# butt_blaster.net
KiCad netlist of a schematic drawn in EAGLE
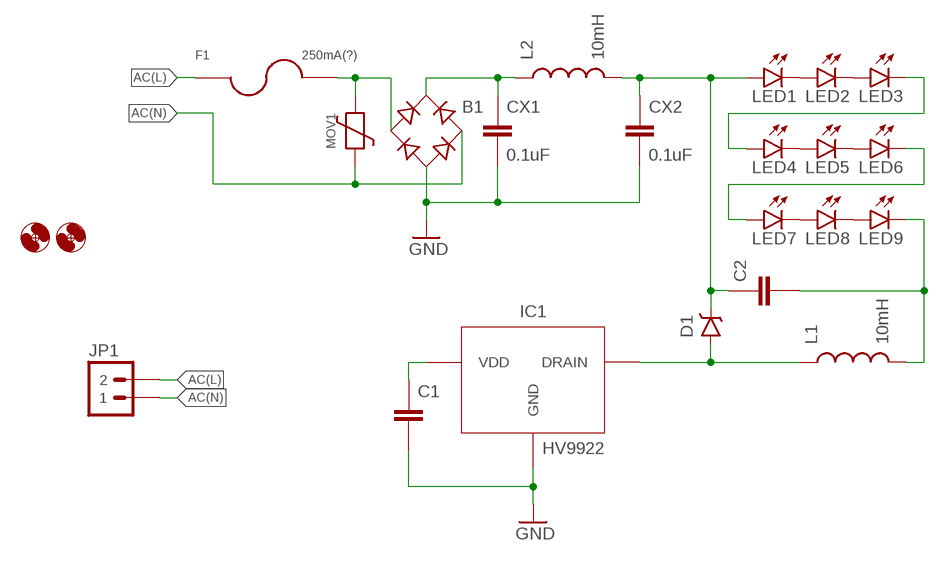
[diagram p0: schematic, sheet 1]

(export (version "E")
  (design (tool "Eeschema 10.0.6"))
  (components
    (comp (ref "B1")
      (value "RB1ANOSUCK")
      (footprint "eagle-import:RB1A-NOSUCK")
      (libsource (lib "eagle-import") (part "RB1ANOSUCK"))
    )
    (comp (ref "C1")
      (value "CAPACITOR-CERAMIC025-024X044")
      (footprint "eagle-import:C025-024X044")
      (libsource (lib "eagle-import") (part "CAPACITOR-CERAMIC025-024X044"))
    )
    (comp (ref "C2")
      (value "CAPACITOR-CERAMIC025-024X044")
      (footprint "eagle-import:C025-024X044")
      (libsource (lib "eagle-import") (part "CAPACITOR-CERAMIC025-024X044"))
    )
    (comp (ref "CX1")
      (value "0.1uF")
      (footprint "eagle-import:XC10B5")
      (libsource (lib "eagle-import") (part "CXXC10B5"))
    )
    (comp (ref "CX2")
      (value "0.1uF")
      (footprint "eagle-import:XC10B5")
      (libsource (lib "eagle-import") (part "CXXC10B5"))
    )
    (comp (ref "D1")
      (value "DIODE-SCHOTTKYPTH-7.68MM")
      (footprint "eagle-import:DIODE-7.68MM")
      (libsource (lib "eagle-import") (part "DIODE-SCHOTTKYPTH-7.68MM"))
    )
    (comp (ref "F1")
      (value "250mA(?)")
      (footprint "eagle-import:TR5")
      (libsource (lib "eagle-import") (part "FUSETR5"))
    )
    (comp (ref "H1")
      (value "HOLE#2")
      (footprint "eagle-import:HOLE-#2")
      (libsource (lib "eagle-import") (part "HOLE#2"))
    )
    (comp (ref "H2")
      (value "HOLE#2")
      (footprint "eagle-import:HOLE-#2")
      (libsource (lib "eagle-import") (part "HOLE#2"))
    )
    (comp (ref "IC1")
      (value "HV9922")
      (footprint "eagle-import:TO-92")
      (libsource (lib "eagle-import") (part "HV9922"))
    )
    (comp (ref "JP1")
      (value "M025MM")
      (footprint "eagle-import:SCREWTERMINAL-5MM-2")
      (libsource (lib "eagle-import") (part "M025MM"))
    )
    (comp (ref "L1")
      (value "10mH")
      (footprint "eagle-import:RLB0912")
      (libsource (lib "eagle-import") (part "INDUCTORRLB0912"))
    )
    (comp (ref "L2")
      (value "10mH")
      (footprint "eagle-import:INDUCTOR-AXIAL-PTH-10.16MM")
      (libsource (lib "eagle-import") (part "INDUCTORAXIAL-PTH-10.16MM"))
    )
    (comp (ref "LED1")
      (value "LED5MM_SHORTPADS")
      (footprint "eagle-import:LED5MM_SHORTPADS")
      (libsource (lib "eagle-import") (part "LED5MM_SHORTPADS"))
    )
    (comp (ref "LED2")
      (value "LED5MM_SHORTPADS")
      (footprint "eagle-import:LED5MM_SHORTPADS")
      (libsource (lib "eagle-import") (part "LED5MM_SHORTPADS"))
    )
    (comp (ref "LED3")
      (value "LED5MM_SHORTPADS")
      (footprint "eagle-import:LED5MM_SHORTPADS")
      (libsource (lib "eagle-import") (part "LED5MM_SHORTPADS"))
    )
    (comp (ref "LED4")
      (value "LED5MM_SHORTPADS")
      (footprint "eagle-import:LED5MM_SHORTPADS")
      (libsource (lib "eagle-import") (part "LED5MM_SHORTPADS"))
    )
    (comp (ref "LED5")
      (value "LED5MM_SHORTPADS")
      (footprint "eagle-import:LED5MM_SHORTPADS")
      (libsource (lib "eagle-import") (part "LED5MM_SHORTPADS"))
    )
    (comp (ref "LED6")
      (value "LED5MM_SHORTPADS")
      (footprint "eagle-import:LED5MM_SHORTPADS")
      (libsource (lib "eagle-import") (part "LED5MM_SHORTPADS"))
    )
    (comp (ref "LED7")
      (value "LED5MM_SHORTPADS")
      (footprint "eagle-import:LED5MM_SHORTPADS")
      (libsource (lib "eagle-import") (part "LED5MM_SHORTPADS"))
    )
    (comp (ref "LED8")
      (value "LED5MM_SHORTPADS")
      (footprint "eagle-import:LED5MM_SHORTPADS")
      (libsource (lib "eagle-import") (part "LED5MM_SHORTPADS"))
    )
    (comp (ref "LED9")
      (value "LED5MM_SHORTPADS")
      (footprint "eagle-import:LED5MM_SHORTPADS")
      (libsource (lib "eagle-import") (part "LED5MM_SHORTPADS"))
    )
    (comp (ref "MOV1")
      (value "VARISITORVAR-5.08MM-PTH")
      (footprint "eagle-import:VAR-5.08MM-PTH")
      (libsource (lib "eagle-import") (part "VARISITORVAR-5.08MM-PTH"))
    )
  )
  (nets
    (net (code "1") (name "AC(L)") (class "Default")
      (node (ref "F1") (pin "1") (pinfunction "1_1") (pintype "bidirectional"))
      (node (ref "JP1") (pin "2") (pinfunction "2_2") (pintype "passive"))
    )
    (net (code "2") (name "AC(N)") (class "Default")
      (node (ref "B1") (pin "AC2") (pinfunction "AC2_AC2") (pintype "passive"))
      (node (ref "JP1") (pin "1") (pinfunction "1_1") (pintype "passive"))
      (node (ref "MOV1") (pin "1") (pinfunction "P$1_1") (pintype "bidirectional"))
    )
    (net (code "3") (name "GND") (class "Default")
      (node (ref "B1") (pin "-") (pinfunction "-_-") (pintype "passive"))
      (node (ref "C1") (pin "2") (pinfunction "2_2") (pintype "passive"))
      (node (ref "CX1") (pin "2") (pinfunction "2_2") (pintype "passive"))
      (node (ref "CX2") (pin "2") (pinfunction "2_2") (pintype "passive"))
      (node (ref "IC1") (pin "2") (pinfunction "GND_2") (pintype "bidirectional"))
    )
    (net (code "4") (name "Net-(D1-C)") (class "Default")
      (node (ref "C2") (pin "1") (pinfunction "1_1") (pintype "passive"))
      (node (ref "CX2") (pin "1") (pinfunction "1_1") (pintype "passive"))
      (node (ref "D1") (pin "K") (pinfunction "C_K") (pintype "passive"))
      (node (ref "L2") (pin "P$2") (pinfunction "2_P$2") (pintype "passive"))
      (node (ref "LED1") (pin "A") (pinfunction "A_A") (pintype "passive"))
    )
    (net (code "5") (name "Net-(IC1-DRAIN)") (class "Default")
      (node (ref "D1") (pin "A") (pinfunction "A_A") (pintype "passive"))
      (node (ref "IC1") (pin "1") (pinfunction "DRAIN_1") (pintype "bidirectional"))
      (node (ref "L1") (pin "1") (pinfunction "1_1") (pintype "passive"))
    )
    (net (code "6") (name "Net-(IC1-VDD)") (class "Default")
      (node (ref "C1") (pin "1") (pinfunction "1_1") (pintype "passive"))
      (node (ref "IC1") (pin "3") (pinfunction "VDD_3") (pintype "bidirectional"))
    )
    (net (code "7") (name "Net-(L2-1)") (class "Default")
      (node (ref "B1") (pin "+") (pinfunction "+_+") (pintype "passive"))
      (node (ref "CX1") (pin "1") (pinfunction "1_1") (pintype "passive"))
      (node (ref "L2") (pin "P$1") (pinfunction "1_P$1") (pintype "passive"))
    )
    (net (code "8") (name "Net-(LED1-C)") (class "Default")
      (node (ref "LED1") (pin "K") (pinfunction "C_K") (pintype "passive"))
      (node (ref "LED2") (pin "A") (pinfunction "A_A") (pintype "passive"))
    )
    (net (code "9") (name "Net-(LED2-C)") (class "Default")
      (node (ref "LED2") (pin "K") (pinfunction "C_K") (pintype "passive"))
      (node (ref "LED3") (pin "A") (pinfunction "A_A") (pintype "passive"))
    )
    (net (code "10") (name "Net-(LED3-C)") (class "Default")
      (node (ref "LED3") (pin "K") (pinfunction "C_K") (pintype "passive"))
      (node (ref "LED4") (pin "A") (pinfunction "A_A") (pintype "passive"))
    )
    (net (code "11") (name "Net-(LED4-C)") (class "Default")
      (node (ref "LED4") (pin "K") (pinfunction "C_K") (pintype "passive"))
      (node (ref "LED5") (pin "A") (pinfunction "A_A") (pintype "passive"))
    )
    (net (code "12") (name "Net-(LED5-C)") (class "Default")
      (node (ref "LED5") (pin "K") (pinfunction "C_K") (pintype "passive"))
      (node (ref "LED6") (pin "A") (pinfunction "A_A") (pintype "passive"))
    )
    (net (code "13") (name "Net-(LED6-C)") (class "Default")
      (node (ref "LED6") (pin "K") (pinfunction "C_K") (pintype "passive"))
      (node (ref "LED7") (pin "A") (pinfunction "A_A") (pintype "passive"))
    )
    (net (code "14") (name "Net-(LED7-C)") (class "Default")
      (node (ref "LED7") (pin "K") (pinfunction "C_K") (pintype "passive"))
      (node (ref "LED8") (pin "A") (pinfunction "A_A") (pintype "passive"))
    )
    (net (code "15") (name "Net-(LED8-C)") (class "Default")
      (node (ref "LED8") (pin "K") (pinfunction "C_K") (pintype "passive"))
      (node (ref "LED9") (pin "A") (pinfunction "A_A") (pintype "passive"))
    )
    (net (code "16") (name "Net-(LED9-C)") (class "Default")
      (node (ref "C2") (pin "2") (pinfunction "2_2") (pintype "passive"))
      (node (ref "L1") (pin "2") (pinfunction "2_2") (pintype "passive"))
      (node (ref "LED9") (pin "K") (pinfunction "C_K") (pintype "passive"))
    )
    (net (code "17") (name "Net-(MOV1-P$2)") (class "Default")
      (node (ref "B1") (pin "AC1") (pinfunction "AC1_AC1") (pintype "passive"))
      (node (ref "F1") (pin "2") (pinfunction "2_2") (pintype "bidirectional"))
      (node (ref "MOV1") (pin "2") (pinfunction "P$2_2") (pintype "bidirectional"))
    )
  )
)
